# rocketavionic.net
KiCad netlist of a schematic drawn in Altium Designer
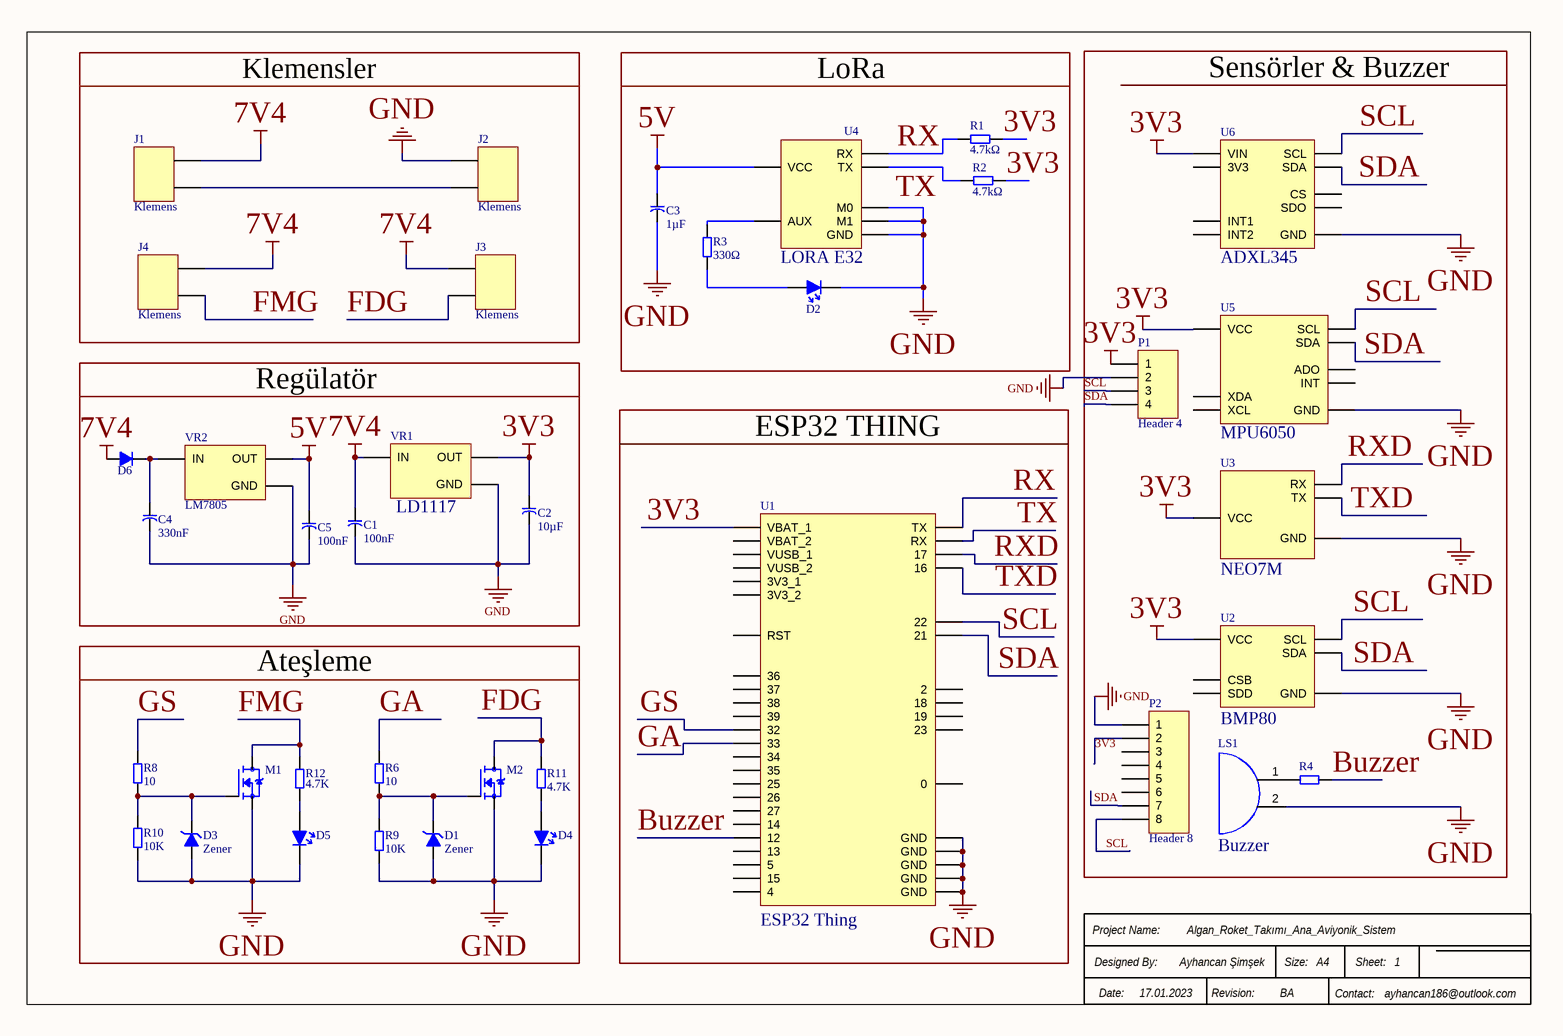
[diagram p0: rocketavionic.SchDoc]

(export (version "E")
  (design (tool "Eeschema 10.0.6"))
  (components
    (comp (ref "C1")
      (value "100nF")
      (footprint "Capacitor")
      (libsource (lib "Integrated_Library2") (part "DCapacitor"))
    )
    (comp (ref "C2")
      (value "10µF")
      (footprint "Capacitor")
      (libsource (lib "Integrated_Library2") (part "DCapacitor"))
    )
    (comp (ref "C3") (value "1µF") (footprint "Capacitor") (libsource (lib "Schlib1") (part "DCapacitor")))
    (comp (ref "C4")
      (value "330nF")
      (footprint "Capacitor")
      (libsource (lib "Integrated_Library2") (part "DCapacitor"))
    )
    (comp (ref "C5")
      (value "100nF")
      (footprint "Capacitor")
      (libsource (lib "Integrated_Library2") (part "DCapacitor"))
    )
    (comp (ref "D1") (value "Zener") (footprint "Zener") (libsource (lib "Schlib1") (part "Zener")))
    (comp (ref "D2") (value "Led") (footprint "LED") (libsource (lib "Integrated_Library2") (part "Led")))
    (comp (ref "D3") (value "Zener") (footprint "Zener") (libsource (lib "Schlib1") (part "Zener")))
    (comp (ref "D4") (value "Led") (footprint "LED") (libsource (lib "Integrated_Library2") (part "Led")))
    (comp (ref "D5") (value "Led") (footprint "LED") (libsource (lib "Integrated_Library2") (part "Led")))
    (comp (ref "D6") (value "e") (footprint "Zener") (libsource (lib "Integrated_Library2") (part "Diode")))
    (comp (ref "J1") (value "Klemens") (footprint "Klemens") (libsource (lib "") (part "Klemens_1")))
    (comp (ref "J2") (value "Klemens") (footprint "Klemens") (libsource (lib "") (part "Klemens_2")))
    (comp (ref "J3")
      (value "Klemens")
      (footprint "Klemens")
      (libsource (lib "Integrated_Library2") (part "Klemens"))
    )
    (comp (ref "J4") (value "Klemens") (footprint "Klemens") (libsource (lib "") (part "Klemens_1")))
    (comp (ref "LS1")
      (value "Buzzer")
      (footprint "Buzzer")
      (libsource (lib "Integrated_Library2") (part "Buzzer"))
    )
    (comp (ref "M1") (value "IRFZ44NPB") (footprint "MOSFET") (libsource (lib "ROCKET") (part "IRFZ44NPB")))
    (comp (ref "M2") (value "IRFZ44NPB") (footprint "MOSFET") (libsource (lib "ROCKET") (part "IRFZ44NPB")))
    (comp (ref "P1")
      (value "Header 4")
      (footprint "HDR1X4")
      (description "Header, 4-Pin")
      (fields (field (name "PUBLISHER") "Altium Limited"))
      (libsource (lib "Miscellaneous Connectors") (part "Header 4"))
    )
    (comp (ref "P2")
      (value "Header 8")
      (footprint "HDR1X8")
      (description "Header, 8-Pin")
      (fields (field (name "PUBLISHER") "Altium Limited"))
      (libsource (lib "Miscellaneous Connectors") (part "Header 8"))
    )
    (comp (ref "R1") (value "4.7kΩ") (footprint "Resistor") (libsource (lib "Schlib1") (part "Resistor")))
    (comp (ref "R2") (value "4.7kΩ") (footprint "Resistor") (libsource (lib "Schlib1") (part "Resistor")))
    (comp (ref "R3") (value "330Ω") (footprint "Resistor") (libsource (lib "Schlib1") (part "Resistor")))
    (comp (ref "R4")
      (value "Resistor")
      (footprint "Resistor")
      (libsource (lib "Integrated_Library2") (part "Resistor"))
    )
    (comp (ref "R6")
      (value "10")
      (footprint "Resistor")
      (libsource (lib "Integrated_Library2") (part "Resistor"))
    )
    (comp (ref "R8")
      (value "10")
      (footprint "Resistor")
      (libsource (lib "Integrated_Library2") (part "Resistor"))
    )
    (comp (ref "R9")
      (value "10K")
      (footprint "Resistor")
      (libsource (lib "Integrated_Library2") (part "Resistor"))
    )
    (comp (ref "R10")
      (value "10K")
      (footprint "Resistor")
      (libsource (lib "Integrated_Library2") (part "Resistor"))
    )
    (comp (ref "R11")
      (value "4.7K")
      (footprint "Resistor")
      (libsource (lib "Integrated_Library2") (part "Resistor"))
    )
    (comp (ref "R12")
      (value "4.7K")
      (footprint "Resistor")
      (libsource (lib "Integrated_Library2") (part "Resistor"))
    )
    (comp (ref "U1")
      (value "ESP32 Thing")
      (footprint "ESP32 THING")
      (description "ESP32 802.11 Wireless LAN/Combo Wireless Module Development Kit")
      (fields (field (name "MANUFACTURER") "SparkFun") (field (name "MANUFACTURER PART NUMBER") "DEV-13907"))
      (libsource (lib "Integrated_Library2") (part "ESP32 Thing"))
    )
    (comp (ref "U2")
      (value "BMP80")
      (footprint "BMP280")
      (description "Washer; #2 Screw Clr; 3/32 ID; 1/4 OD; 1/32 Height; Nylon")
      (fields (field (name "MANUFACTURER") "Bosch") (field (name "MANUFACTURER PART NUMBER") "BMP280"))
      (libsource (lib "Integrated_Library2") (part "BMP80"))
    )
    (comp (ref "U3")
      (value "NEO7M")
      (footprint "NEO6MV2")
      (description "U#NEO-6M Gps Module U-BLOX6 SMD24P")
      (fields (field (name "MANUFACTURER") "u-blox") (field (name "MANUFACTURER PART NUMBER") "NEO-6M-0"))
      (libsource (lib "Integrated_Library2") (part "NEO6MV2"))
    )
    (comp (ref "U4")
      (value "LORA E32")
      (footprint "LORAE32")
      (description "WiFi-Modul 802.11/BT 2, 4-2, 5GHz 150Mb/s")
      (fields
        (field (name "MANUFACTURER") "Espressif Systems")
        (field (name "MANUFACTURER PART NUMBER") "ESP32-S3-WROOM-1-N16R8")
      )
      (libsource (lib "Integrated_Library2") (part "LORA E32"))
    )
    (comp (ref "U5")
      (value "MPU6050")
      (footprint "MPU6050")
      (description "IMU ACCEL/GYRO 3-AXIS I2C 24QFN")
      (fields
        (field (name "MANUFACTURER") "TDK InvenSense")
        (field (name "MANUFACTURER PART NUMBER") "MPU-6050")
      )
      (libsource (lib "Schlib1") (part "MPU6050"))
    )
    (comp (ref "U6")
      (value "ADXL345")
      (footprint "ADXL345")
      (description "Accelerometer Triple ±2/±4/±8/±16g 2V to 3.6V 14-Pin LGA T/R")
      (fields
        (field (name "MANUFACTURER") "Analog Devices")
        (field (name "MANUFACTURER PART NUMBER") "ADXL345TCCZ-EP-RL7")
      )
      (libsource (lib "Schlib1") (part "ADXL345"))
    )
    (comp (ref "VR1")
      (value "LD1117")
      (footprint "LD1117")
      (description "LDO Regulator Pos 3.3V 1.3A 3-Pin(3+Tab) TO-220 Tube (Alt: LD1117V33C)")
      (fields
        (field (name "MANUFACTURER") "STMicroelectronics")
        (field (name "MANUFACTURER PART NUMBER") "LD1117V33C")
      )
      (libsource (lib "Schlib1") (part "LD1117"))
    )
    (comp (ref "VR2")
      (value "LM7805")
      (footprint "LM7805")
      (description "LM78XX Series 5 V Fixed Output 1 A 3-Terminal LDO Voltage Regulator - TO-220")
      (fields
        (field (name "MANUFACTURER") "ON Semiconductor / Fairchild")
        (field (name "MANUFACTURER PART NUMBER") "LM7805CT")
      )
      (libsource (lib "Integrated_Library2") (part "LM7805"))
    )
  )
  (nets
    (net (code "1") (name "/Buzzer") (class "Default")
      (node (ref "R4") (pin "2") (pinfunction "2_2") (pintype "passive"))
      (node (ref "U1") (pin "12") (pinfunction "12_12") (pintype "passive"))
    )
    (net (code "2") (name "/FDG") (class "Default")
      (node (ref "J3") (pin "1") (pinfunction "1_1") (pintype "passive"))
      (node (ref "M2") (pin "2") (pinfunction "D_2") (pintype "passive"))
      (node (ref "R11") (pin "1") (pinfunction "1_1") (pintype "passive"))
    )
    (net (code "3") (name "/FMG") (class "Default")
      (node (ref "J4") (pin "1") (pinfunction "1_1") (pintype "passive"))
      (node (ref "M1") (pin "2") (pinfunction "D_2") (pintype "passive"))
      (node (ref "R12") (pin "1") (pinfunction "1_1") (pintype "passive"))
    )
    (net (code "4") (name "/GA") (class "Default")
      (node (ref "R6") (pin "2") (pinfunction "2_2") (pintype "passive"))
      (node (ref "U1") (pin "33") (pinfunction "33_33") (pintype "passive"))
    )
    (net (code "5") (name "/GS") (class "Default")
      (node (ref "R8") (pin "2") (pinfunction "2_2") (pintype "passive"))
      (node (ref "U1") (pin "32") (pinfunction "32_32") (pintype "passive"))
    )
    (net (code "6") (name "/RX") (class "Default")
      (node (ref "R1") (pin "1") (pinfunction "1_1") (pintype "passive"))
      (node (ref "U1") (pin "TX") (pinfunction "TX_TX") (pintype "passive"))
      (node (ref "U4") (pin "5") (pinfunction "RX_5") (pintype "passive"))
    )
    (net (code "7") (name "/RXD") (class "Default")
      (node (ref "U1") (pin "17") (pinfunction "17_17") (pintype "passive"))
      (node (ref "U3") (pin "2") (pinfunction "RX_2") (pintype "passive"))
    )
    (net (code "8") (name "/SCL") (class "Default")
      (node (ref "P1") (pin "3") (pinfunction "3_3") (pintype "passive"))
      (node (ref "P2") (pin "8") (pinfunction "8_8") (pintype "passive"))
      (node (ref "U1") (pin "22") (pinfunction "22_22") (pintype "passive"))
      (node (ref "U2") (pin "3") (pinfunction "SCL_3") (pintype "passive"))
      (node (ref "U5") (pin "3") (pinfunction "SCL_3") (pintype "passive"))
      (node (ref "U6") (pin "4") (pinfunction "SCL_4") (pintype "passive"))
    )
    (net (code "9") (name "/SDA") (class "Default")
      (node (ref "P1") (pin "4") (pinfunction "4_4") (pintype "passive"))
      (node (ref "P2") (pin "7") (pinfunction "7_7") (pintype "passive"))
      (node (ref "U1") (pin "21") (pinfunction "21_21") (pintype "passive"))
      (node (ref "U2") (pin "4") (pinfunction "SDA_4") (pintype "passive"))
      (node (ref "U5") (pin "4") (pinfunction "SDA_4") (pintype "passive"))
      (node (ref "U6") (pin "5") (pinfunction "SDA_5") (pintype "passive"))
    )
    (net (code "10") (name "/TX") (class "Default")
      (node (ref "R2") (pin "1") (pinfunction "1_1") (pintype "passive"))
      (node (ref "U1") (pin "RX") (pinfunction "RX_RX") (pintype "passive"))
      (node (ref "U4") (pin "4") (pinfunction "TX_4") (pintype "passive"))
    )
    (net (code "11") (name "/TXD") (class "Default")
      (node (ref "U1") (pin "16") (pinfunction "16_16") (pintype "passive"))
      (node (ref "U3") (pin "3") (pinfunction "TX_3") (pintype "passive"))
    )
    (net (code "12") (name "3V3") (class "Default")
      (node (ref "C2") (pin "1") (pinfunction "1_1") (pintype "passive"))
      (node (ref "P1") (pin "1") (pinfunction "1_1") (pintype "passive"))
      (node (ref "P2") (pin "2") (pinfunction "2_2") (pintype "passive"))
      (node (ref "R1") (pin "2") (pinfunction "2_2") (pintype "passive"))
      (node (ref "R2") (pin "2") (pinfunction "2_2") (pintype "passive"))
      (node (ref "U1") (pin "VBAT_1") (pinfunction "VBAT_1_VBAT_1") (pintype "passive"))
      (node (ref "U2") (pin "1") (pinfunction "VCC_1") (pintype "passive"))
      (node (ref "U3") (pin "1") (pinfunction "VCC_1") (pintype "passive"))
      (node (ref "U5") (pin "1") (pinfunction "VCC_1") (pintype "passive"))
      (node (ref "U6") (pin "0") (pinfunction "VIN_0") (pintype "passive"))
      (node (ref "VR1") (pin "2") (pinfunction "OUT_2") (pintype "passive"))
    )
    (net (code "13") (name "5V") (class "Default")
      (node (ref "C3") (pin "1") (pinfunction "1_1") (pintype "passive"))
      (node (ref "C5") (pin "1") (pinfunction "1_1") (pintype "passive"))
      (node (ref "U4") (pin "2") (pinfunction "VCC_2") (pintype "passive"))
      (node (ref "VR2") (pin "3") (pinfunction "OUT_3") (pintype "passive"))
    )
    (net (code "14") (name "7V4") (class "Default")
      (node (ref "C1") (pin "1") (pinfunction "1_1") (pintype "passive"))
      (node (ref "D6") (pin "1") (pinfunction "1_1") (pintype "passive"))
      (node (ref "J1") (pin "0") (pinfunction "0_0") (pintype "passive"))
      (node (ref "J3") (pin "0") (pinfunction "0_0") (pintype "passive"))
      (node (ref "J4") (pin "0") (pinfunction "0_0") (pintype "passive"))
      (node (ref "VR1") (pin "1") (pinfunction "IN_1") (pintype "passive"))
    )
    (net (code "15") (name "GND") (class "Default")
      (node (ref "C1") (pin "2") (pinfunction "2_2") (pintype "passive"))
      (node (ref "C2") (pin "2") (pinfunction "2_2") (pintype "passive"))
      (node (ref "C3") (pin "2") (pinfunction "2_2") (pintype "passive"))
      (node (ref "C4") (pin "2") (pinfunction "2_2") (pintype "passive"))
      (node (ref "C5") (pin "2") (pinfunction "2_2") (pintype "passive"))
      (node (ref "D1") (pin "1") (pinfunction "1_1") (pintype "passive"))
      (node (ref "D2") (pin "1") (pinfunction "1_1") (pintype "power_in"))
      (node (ref "D3") (pin "1") (pinfunction "1_1") (pintype "passive"))
      (node (ref "D4") (pin "1") (pinfunction "1_1") (pintype "power_in"))
      (node (ref "D5") (pin "1") (pinfunction "1_1") (pintype "power_in"))
      (node (ref "J2") (pin "1") (pinfunction "1_1") (pintype "passive"))
      (node (ref "LS1") (pin "2") (pinfunction "2_2") (pintype "passive"))
      (node (ref "M1") (pin "3") (pinfunction "S_3") (pintype "passive"))
      (node (ref "M2") (pin "3") (pinfunction "S_3") (pintype "passive"))
      (node (ref "P1") (pin "2") (pinfunction "2_2") (pintype "passive"))
      (node (ref "P2") (pin "1") (pinfunction "1_1") (pintype "passive"))
      (node (ref "R10") (pin "2") (pinfunction "2_2") (pintype "passive"))
      (node (ref "R9") (pin "2") (pinfunction "2_2") (pintype "passive"))
      (node (ref "U1") (pin "GND_1") (pinfunction "GND_GND_1") (pintype "passive"))
      (node (ref "U1") (pin "GND_2") (pinfunction "GND_GND_2") (pintype "passive"))
      (node (ref "U1") (pin "GND_3") (pinfunction "GND_GND_3") (pintype "passive"))
      (node (ref "U1") (pin "GND_4") (pinfunction "GND_GND_4") (pintype "passive"))
      (node (ref "U1") (pin "GND_5") (pinfunction "GND_GND_5") (pintype "passive"))
      (node (ref "U2") (pin "2") (pinfunction "GND_2") (pintype "passive"))
      (node (ref "U3") (pin "4") (pinfunction "GND_4") (pintype "passive"))
      (node (ref "U4") (pin "1") (pinfunction "GND_1") (pintype "passive"))
      (node (ref "U4") (pin "6") (pinfunction "M1_6") (pintype "passive"))
      (node (ref "U4") (pin "7") (pinfunction "M0_7") (pintype "passive"))
      (node (ref "U5") (pin "2") (pinfunction "GND_2") (pintype "passive"))
      (node (ref "U6") (pin "7") (pinfunction "GND_7") (pintype "passive"))
      (node (ref "VR1") (pin "3") (pinfunction "GND_3") (pintype "passive"))
      (node (ref "VR2") (pin "2") (pinfunction "GND_2") (pintype "passive"))
    )
    (net (code "16") (name "Net-(D2-Pad2)") (class "Default")
      (node (ref "D2") (pin "2") (pinfunction "2_2") (pintype "power_in"))
      (node (ref "R3") (pin "1") (pinfunction "1_1") (pintype "passive"))
    )
    (net (code "17") (name "Net-(D4-Pad2)") (class "Default")
      (node (ref "D4") (pin "2") (pinfunction "2_2") (pintype "power_in"))
      (node (ref "R11") (pin "2") (pinfunction "2_2") (pintype "passive"))
    )
    (net (code "18") (name "Net-(D5-Pad2)") (class "Default")
      (node (ref "D5") (pin "2") (pinfunction "2_2") (pintype "power_in"))
      (node (ref "R12") (pin "2") (pinfunction "2_2") (pintype "passive"))
    )
    (net (code "19") (name "Net-(J1-Pad1)") (class "Default")
      (node (ref "J1") (pin "1") (pinfunction "1_1") (pintype "passive"))
      (node (ref "J2") (pin "0") (pinfunction "0_0") (pintype "passive"))
    )
    (net (code "20") (name "Net-(LS1-Pad1)") (class "Default")
      (node (ref "LS1") (pin "1") (pinfunction "1_1") (pintype "passive"))
      (node (ref "R4") (pin "1") (pinfunction "1_1") (pintype "passive"))
    )
    (net (code "21") (name "Net-(M1-G)") (class "Default")
      (node (ref "D3") (pin "2") (pinfunction "2_2") (pintype "passive"))
      (node (ref "M1") (pin "1") (pinfunction "G_1") (pintype "passive"))
      (node (ref "R10") (pin "1") (pinfunction "1_1") (pintype "passive"))
      (node (ref "R8") (pin "1") (pinfunction "1_1") (pintype "passive"))
    )
    (net (code "22") (name "Net-(M2-G)") (class "Default")
      (node (ref "D1") (pin "2") (pinfunction "2_2") (pintype "passive"))
      (node (ref "M2") (pin "1") (pinfunction "G_1") (pintype "passive"))
      (node (ref "R6") (pin "1") (pinfunction "1_1") (pintype "passive"))
      (node (ref "R9") (pin "1") (pinfunction "1_1") (pintype "passive"))
    )
    (net (code "23") (name "Net-(U4-AUX)") (class "Default")
      (node (ref "R3") (pin "2") (pinfunction "2_2") (pintype "passive"))
      (node (ref "U4") (pin "3") (pinfunction "AUX_3") (pintype "passive"))
    )
    (net (code "24") (name "Net-(VR2-IN)") (class "Default")
      (node (ref "C4") (pin "1") (pinfunction "1_1") (pintype "passive"))
      (node (ref "D6") (pin "2") (pinfunction "2_2") (pintype "passive"))
      (node (ref "VR2") (pin "1") (pinfunction "IN_1") (pintype "passive"))
    )
    (net (code "25") (name "unconnected-(P2-Pad3)") (class "Default")
      (node (ref "P2") (pin "3") (pinfunction "3_3") (pintype "passive"))
    )
    (net (code "26") (name "unconnected-(P2-Pad4)") (class "Default")
      (node (ref "P2") (pin "4") (pinfunction "4_4") (pintype "passive"))
    )
    (net (code "27") (name "unconnected-(P2-Pad5)") (class "Default")
      (node (ref "P2") (pin "5") (pinfunction "5_5") (pintype "passive"))
    )
    (net (code "28") (name "unconnected-(P2-Pad6)") (class "Default")
      (node (ref "P2") (pin "6") (pinfunction "6_6") (pintype "passive"))
    )
    (net (code "29") (name "unconnected-(U1-Pad0)") (class "Default")
      (node (ref "U1") (pin "0") (pinfunction "0_0") (pintype "passive"))
    )
    (net (code "30") (name "unconnected-(U1-Pad2)") (class "Default")
      (node (ref "U1") (pin "2") (pinfunction "2_2") (pintype "passive"))
    )
    (net (code "31") (name "unconnected-(U1-Pad3V3_1)") (class "Default")
      (node (ref "U1") (pin "3V3_1") (pinfunction "3V3_1_3V3_1") (pintype "passive"))
    )
    (net (code "32") (name "unconnected-(U1-Pad3V3_2)") (class "Default")
      (node (ref "U1") (pin "3V3_2") (pinfunction "3V3_2_3V3_2") (pintype "passive"))
    )
    (net (code "33") (name "unconnected-(U1-Pad4)") (class "Default")
      (node (ref "U1") (pin "4") (pinfunction "4_4") (pintype "passive"))
    )
    (net (code "34") (name "unconnected-(U1-Pad5)") (class "Default")
      (node (ref "U1") (pin "5") (pinfunction "5_5") (pintype "passive"))
    )
    (net (code "35") (name "unconnected-(U1-Pad13)") (class "Default")
      (node (ref "U1") (pin "13") (pinfunction "13_13") (pintype "passive"))
    )
    (net (code "36") (name "unconnected-(U1-Pad14)") (class "Default")
      (node (ref "U1") (pin "14") (pinfunction "14_14") (pintype "passive"))
    )
    (net (code "37") (name "unconnected-(U1-Pad15)") (class "Default")
      (node (ref "U1") (pin "15") (pinfunction "15_15") (pintype "passive"))
    )
    (net (code "38") (name "unconnected-(U1-Pad18)") (class "Default")
      (node (ref "U1") (pin "18") (pinfunction "18_18") (pintype "passive"))
    )
    (net (code "39") (name "unconnected-(U1-Pad19)") (class "Default")
      (node (ref "U1") (pin "19") (pinfunction "19_19") (pintype "passive"))
    )
    (net (code "40") (name "unconnected-(U1-Pad23)") (class "Default")
      (node (ref "U1") (pin "23") (pinfunction "23_23") (pintype "passive"))
    )
    (net (code "41") (name "unconnected-(U1-Pad25)") (class "Default")
      (node (ref "U1") (pin "25") (pinfunction "25_25") (pintype "passive"))
    )
    (net (code "42") (name "unconnected-(U1-Pad26)") (class "Default")
      (node (ref "U1") (pin "26") (pinfunction "26_26") (pintype "passive"))
    )
    (net (code "43") (name "unconnected-(U1-Pad27)") (class "Default")
      (node (ref "U1") (pin "27") (pinfunction "27_27") (pintype "passive"))
    )
    (net (code "44") (name "unconnected-(U1-Pad34)") (class "Default")
      (node (ref "U1") (pin "34") (pinfunction "34_34") (pintype "passive"))
    )
    (net (code "45") (name "unconnected-(U1-Pad35)") (class "Default")
      (node (ref "U1") (pin "35") (pinfunction "35_35") (pintype "passive"))
    )
    (net (code "46") (name "unconnected-(U1-Pad36)") (class "Default")
      (node (ref "U1") (pin "36") (pinfunction "36_36") (pintype "passive"))
    )
    (net (code "47") (name "unconnected-(U1-Pad37)") (class "Default")
      (node (ref "U1") (pin "37") (pinfunction "37_37") (pintype "passive"))
    )
    (net (code "48") (name "unconnected-(U1-Pad38)") (class "Default")
      (node (ref "U1") (pin "38") (pinfunction "38_38") (pintype "passive"))
    )
    (net (code "49") (name "unconnected-(U1-Pad39)") (class "Default")
      (node (ref "U1") (pin "39") (pinfunction "39_39") (pintype "passive"))
    )
    (net (code "50") (name "unconnected-(U1-PadRST)") (class "Default")
      (node (ref "U1") (pin "RST") (pinfunction "RST_RST") (pintype "passive"))
    )
    (net (code "51") (name "unconnected-(U1-PadVBAT_2)") (class "Default")
      (node (ref "U1") (pin "VBAT_2") (pinfunction "VBAT_2_VBAT_2") (pintype "passive"))
    )
    (net (code "52") (name "unconnected-(U1-PadVUSB_1)") (class "Default")
      (node (ref "U1") (pin "VUSB_1") (pinfunction "VUSB_1_VUSB_1") (pintype "passive"))
    )
    (net (code "53") (name "unconnected-(U1-PadVUSB_2)") (class "Default")
      (node (ref "U1") (pin "VUSB_2") (pinfunction "VUSB_2_VUSB_2") (pintype "passive"))
    )
    (net (code "54") (name "unconnected-(U2-CSB-Pad5)") (class "Default")
      (node (ref "U2") (pin "5") (pinfunction "CSB_5") (pintype "passive"))
    )
    (net (code "55") (name "unconnected-(U2-SDD-Pad6)") (class "Default")
      (node (ref "U2") (pin "6") (pinfunction "SDD_6") (pintype "passive"))
    )
    (net (code "56") (name "unconnected-(U5-ADO-Pad7)") (class "Default")
      (node (ref "U5") (pin "7") (pinfunction "ADO_7") (pintype "passive"))
    )
    (net (code "57") (name "unconnected-(U5-INT-Pad8)") (class "Default")
      (node (ref "U5") (pin "8") (pinfunction "INT_8") (pintype "passive"))
    )
    (net (code "58") (name "unconnected-(U5-XCL-Pad6)") (class "Default")
      (node (ref "U5") (pin "6") (pinfunction "XCL_6") (pintype "passive"))
    )
    (net (code "59") (name "unconnected-(U5-XDA-Pad5)") (class "Default")
      (node (ref "U5") (pin "5") (pinfunction "XDA_5") (pintype "passive"))
    )
    (net (code "60") (name "unconnected-(U6-3V3-Pad1)") (class "Default")
      (node (ref "U6") (pin "1") (pinfunction "3V3_1") (pintype "passive"))
    )
    (net (code "61") (name "unconnected-(U6-CS-Pad6)") (class "Default")
      (node (ref "U6") (pin "6") (pinfunction "CS_6") (pintype "passive"))
    )
    (net (code "62") (name "unconnected-(U6-INT1-Pad2)") (class "Default")
      (node (ref "U6") (pin "2") (pinfunction "INT1_2") (pintype "passive"))
    )
    (net (code "63") (name "unconnected-(U6-INT2-Pad3)") (class "Default")
      (node (ref "U6") (pin "3") (pinfunction "INT2_3") (pintype "passive"))
    )
    (net (code "64") (name "unconnected-(U6-SDO-Pad8)") (class "Default")
      (node (ref "U6") (pin "8") (pinfunction "SDO_8") (pintype "passive"))
    )
  )
)
